# PCB_tutorial.net
KiCad netlist of a schematic drawn in Altium Designer
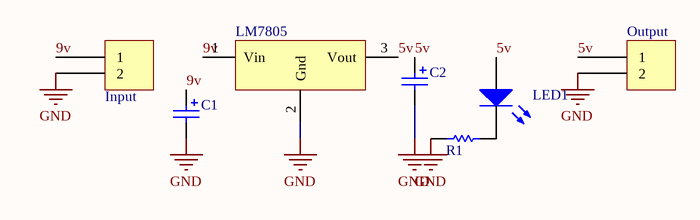
[diagram p0: PCB_tutorial.SchDoc]

(export (version "E")
  (design (tool "Eeschema 10.0.6"))
  (components
    (comp (ref "C1")
      (value "Cap Polar 100uF")
      (footprint "Cap 100uF")
      (libsource (lib "GAPlib_DEVICES") (part "Cap 100uF"))
    )
    (comp (ref "C2")
      (value "Cap Polar 100uF")
      (footprint "Cap 100uF")
      (libsource (lib "GAPlib_DEVICES") (part "Cap 100uF"))
    )
    (comp (ref "Input")
      (value "Terminal Barrier Besar 2 PIN")
      (footprint "Terminal Barrier Besar 2 PIN")
      (description "Tanpa Kuping")
      (libsource (lib "GAPlib_CONNECTOR") (part "Terminal Barrier Besar 2 PIN"))
    )
    (comp (ref "LED1")
      (value "LED 5mm")
      (footprint "LED 5mm")
      (libsource (lib "GAPlib_DEVICES") (part "LED 5mm"))
    )
    (comp (ref "LM7805")
      (value "78XX/79XX - with Heatsink")
      (footprint "78XX/79XX HEATSINK")
      (libsource (lib "GAPlib_DEVICES") (part "78XX/79XX-heatsink"))
    )
    (comp (ref "Output")
      (value "Terminal Barrier Besar 2 PIN")
      (footprint "Terminal Barrier Besar 2 PIN")
      (description "Tanpa Kuping")
      (libsource (lib "GAPlib_CONNECTOR") (part "Terminal Barrier Besar 2 PIN"))
    )
    (comp (ref "R1")
      (value "Resistor 0.25W")
      (footprint "Resistor 0.25W")
      (libsource (lib "GAPlib_DEVICES") (part "Resistor 0.25W"))
    )
  )
  (nets
    (net (code "1") (name "/5v") (class "Default")
      (node (ref "C2") (pin "1") (pinfunction "1_1") (pintype "passive"))
      (node (ref "LED1") (pin "1") (pinfunction "A_1") (pintype "passive"))
      (node (ref "LM7805") (pin "3") (pinfunction "Vout_3") (pintype "passive"))
      (node (ref "Output") (pin "1") (pinfunction "1_1") (pintype "passive"))
    )
    (net (code "2") (name "/9v") (class "Default")
      (node (ref "C1") (pin "1") (pinfunction "1_1") (pintype "passive"))
      (node (ref "Input") (pin "1") (pinfunction "1_1") (pintype "passive"))
      (node (ref "LM7805") (pin "1") (pinfunction "Vin_1") (pintype "passive"))
    )
    (net (code "3") (name "GND") (class "Default")
      (node (ref "C1") (pin "2") (pinfunction "2_2") (pintype "passive"))
      (node (ref "C2") (pin "2") (pinfunction "2_2") (pintype "passive"))
      (node (ref "Input") (pin "2") (pinfunction "2_2") (pintype "passive"))
      (node (ref "LM7805") (pin "2") (pinfunction "Gnd_2") (pintype "passive"))
      (node (ref "Output") (pin "2") (pinfunction "2_2") (pintype "passive"))
      (node (ref "R1") (pin "2") (pinfunction "2_2") (pintype "passive"))
    )
    (net (code "4") (name "Net-(LED1-K)") (class "Default")
      (node (ref "LED1") (pin "2") (pinfunction "K_2") (pintype "passive"))
      (node (ref "R1") (pin "1") (pinfunction "1_1") (pintype "passive"))
    )
  )
)
